# TB6560.net
KiCad netlist of a schematic drawn in Altium Designer
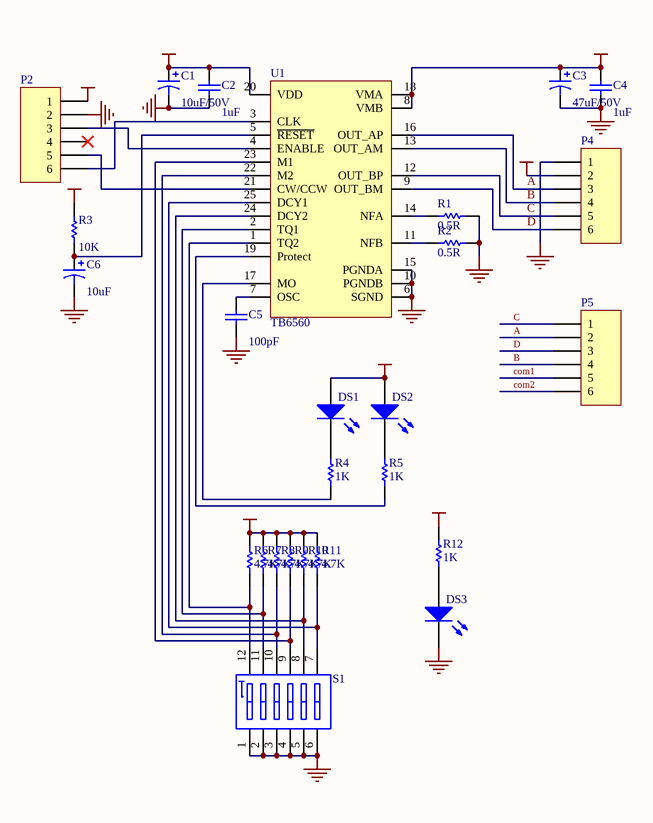
[diagram p0: 微步進驅動器TB6560.SCHDOC]

(export (version "E")
  (design (tool "Eeschema 10.0.6"))
  (components
    (comp (ref "C1")
      (value "10uF/50V")
      (footprint "CAPPR5-5x5")
      (description "Polarized Capacitor (Radial)")
      (fields (field (name "Comment") "Cap Pol1") (field (name "PUBLISHER") "Altium Limited"))
      (libsource (lib "Miscellaneous Devices") (part "Cap Pol1"))
    )
    (comp (ref "C2")
      (value "1uF")
      (footprint "CAPR5.08-7.8x3.2")
      (description "Capacitor")
      (fields (field (name "Comment") "Cap") (field (name "PUBLISHER") "Altium Limited"))
      (libsource (lib "Miscellaneous Devices") (part "Cap"))
    )
    (comp (ref "C3")
      (value "47uF/50V")
      (footprint "CAPPR5-5x5")
      (description "Polarized Capacitor (Radial)")
      (fields (field (name "Comment") "Cap Pol1") (field (name "PUBLISHER") "Altium Limited"))
      (libsource (lib "Miscellaneous Devices") (part "Cap Pol1"))
    )
    (comp (ref "C4")
      (value "1uF")
      (footprint "CAPR5.08-7.8x3.2")
      (description "Capacitor")
      (fields (field (name "Comment") "Cap") (field (name "PUBLISHER") "Altium Limited"))
      (libsource (lib "Miscellaneous Devices") (part "Cap"))
    )
    (comp (ref "C5")
      (value "100pF")
      (footprint "CAPR5.08-7.8x3.2")
      (description "Capacitor")
      (fields (field (name "Comment") "Cap") (field (name "PUBLISHER") "Altium Limited"))
      (libsource (lib "Miscellaneous Devices") (part "Cap"))
    )
    (comp (ref "C6")
      (value "10uF")
      (footprint "CAPPR5-5x5")
      (description "Polarized Capacitor (Radial)")
      (fields (field (name "Comment") "Cap Pol1") (field (name "PUBLISHER") "Altium Limited"))
      (libsource (lib "Miscellaneous Devices") (part "Cap Pol1"))
    )
    (comp (ref "DS1")
      (value "LED1")
      (footprint "LED 3mm T")
      (description "Typical RED GaAs LED")
      (fields (field (name "PUBLISHER") "Altium Limited"))
      (libsource (lib "Miscellaneous Devices") (part "LED1"))
    )
    (comp (ref "DS2")
      (value "LED1")
      (footprint "LED 3mm T")
      (description "Typical RED GaAs LED")
      (fields (field (name "PUBLISHER") "Altium Limited"))
      (libsource (lib "Miscellaneous Devices") (part "LED1"))
    )
    (comp (ref "DS3")
      (value "LED1")
      (footprint "LED 3mm T")
      (description "Typical RED GaAs LED")
      (fields (field (name "PUBLISHER") "Altium Limited"))
      (libsource (lib "Miscellaneous Devices") (part "LED1"))
    )
    (comp (ref "P2")
      (value "Header 6")
      (footprint "HDR1X6")
      (description "Header, 6-Pin")
      (fields (field (name "PUBLISHER") "Altium Limited"))
      (libsource (lib "") (part "Header 6_1"))
    )
    (comp (ref "P4")
      (value "Header 6")
      (footprint "6pinºÝ¤l-1")
      (description "Header, 6-Pin")
      (fields (field (name "PUBLISHER") "Altium Limited"))
      (libsource (lib "Miscellaneous Connectors") (part "Header 6"))
    )
    (comp (ref "P5")
      (value "Header 6")
      (footprint "HDR1X6")
      (description "Header, 6-Pin")
      (fields (field (name "PUBLISHER") "Altium Limited"))
      (libsource (lib "Miscellaneous Connectors") (part "Header 6"))
    )
    (comp (ref "R1")
      (value "0.5R")
      (footprint "¹qªý5.08mm")
      (description "Resistor")
      (fields (field (name "Comment") "Res1") (field (name "PUBLISHER") "Altium Limited"))
      (libsource (lib "Miscellaneous Devices") (part "Res1"))
    )
    (comp (ref "R2")
      (value "0.5R")
      (footprint "¹qªý5.08mm")
      (description "Resistor")
      (fields (field (name "Comment") "Res1") (field (name "PUBLISHER") "Altium Limited"))
      (libsource (lib "Miscellaneous Devices") (part "Res1"))
    )
    (comp (ref "R3")
      (value "10K")
      (footprint "AXIAL-0.3")
      (description "Resistor")
      (fields (field (name "Comment") "Res1") (field (name "PUBLISHER") "Altium Limited"))
      (libsource (lib "Miscellaneous Devices") (part "Res1"))
    )
    (comp (ref "R4")
      (value "1K")
      (footprint "AXIAL-0.3")
      (description "Resistor")
      (fields (field (name "Comment") "Res1") (field (name "PUBLISHER") "Altium Limited"))
      (libsource (lib "Miscellaneous Devices") (part "Res1"))
    )
    (comp (ref "R5")
      (value "1K")
      (footprint "AXIAL-0.3")
      (description "Resistor")
      (fields (field (name "Comment") "Res1") (field (name "PUBLISHER") "Altium Limited"))
      (libsource (lib "Miscellaneous Devices") (part "Res1"))
    )
    (comp (ref "R6")
      (value "4.7K")
      (footprint "AXIAL-0.3")
      (description "Resistor")
      (fields (field (name "Comment") "Res1") (field (name "PUBLISHER") "Altium Limited"))
      (libsource (lib "Miscellaneous Devices") (part "Res1"))
    )
    (comp (ref "R7")
      (value "4.7K")
      (footprint "AXIAL-0.3")
      (description "Resistor")
      (fields (field (name "Comment") "Res1") (field (name "PUBLISHER") "Altium Limited"))
      (libsource (lib "Miscellaneous Devices") (part "Res1"))
    )
    (comp (ref "R8")
      (value "4.7K")
      (footprint "AXIAL-0.3")
      (description "Resistor")
      (fields (field (name "Comment") "Res1") (field (name "PUBLISHER") "Altium Limited"))
      (libsource (lib "Miscellaneous Devices") (part "Res1"))
    )
    (comp (ref "R9")
      (value "4.7K")
      (footprint "AXIAL-0.3")
      (description "Resistor")
      (fields (field (name "Comment") "Res1") (field (name "PUBLISHER") "Altium Limited"))
      (libsource (lib "Miscellaneous Devices") (part "Res1"))
    )
    (comp (ref "R10")
      (value "4.7K")
      (footprint "AXIAL-0.3")
      (description "Resistor")
      (fields (field (name "Comment") "Res1") (field (name "PUBLISHER") "Altium Limited"))
      (libsource (lib "Miscellaneous Devices") (part "Res1"))
    )
    (comp (ref "R11")
      (value "4.7K")
      (footprint "AXIAL-0.3")
      (description "Resistor")
      (fields (field (name "Comment") "Res1") (field (name "PUBLISHER") "Altium Limited"))
      (libsource (lib "Miscellaneous Devices") (part "Res1"))
    )
    (comp (ref "R12")
      (value "1K")
      (footprint "AXIAL-0.3")
      (description "Resistor")
      (fields (field (name "Comment") "Res1") (field (name "PUBLISHER") "Altium Limited"))
      (libsource (lib "Miscellaneous Devices") (part "Res1"))
    )
    (comp (ref "S1")
      (value "SW DIP-6")
      (footprint "DIP-12/SW")
      (description "DIP Switch")
      (fields (field (name "PUBLISHER") "Altium Limited"))
      (libsource (lib "Miscellaneous Devices") (part "SW DIP-6"))
    )
    (comp (ref "U1") (value "TB6560") (footprint "TB6560AHQ") (libsource (lib "mydata") (part "TB6560")))
  )
  (nets
    (net (code "1") (name "+12") (class "Default")
      (node (ref "C3") (pin "1") (pinfunction "1_1") (pintype "passive"))
      (node (ref "C4") (pin "2") (pinfunction "2_2") (pintype "passive"))
      (node (ref "P4") (pin "2") (pinfunction "2_2") (pintype "passive"))
      (node (ref "U1") (pin "18") (pinfunction "VMA_18") (pintype "passive"))
      (node (ref "U1") (pin "8") (pinfunction "VMB_8") (pintype "passive"))
    )
    (net (code "2") (name "/A") (class "Default")
      (node (ref "P4") (pin "3") (pinfunction "3_3") (pintype "passive"))
      (node (ref "P5") (pin "2") (pinfunction "2_2") (pintype "passive"))
      (node (ref "U1") (pin "16") (pinfunction "OUT_AP_16") (pintype "passive"))
    )
    (net (code "3") (name "/B") (class "Default")
      (node (ref "P4") (pin "4") (pinfunction "4_4") (pintype "passive"))
      (node (ref "P5") (pin "4") (pinfunction "4_4") (pintype "passive"))
      (node (ref "U1") (pin "13") (pinfunction "OUT_AM_13") (pintype "passive"))
    )
    (net (code "4") (name "/C") (class "Default")
      (node (ref "P4") (pin "5") (pinfunction "5_5") (pintype "passive"))
      (node (ref "P5") (pin "1") (pinfunction "1_1") (pintype "passive"))
      (node (ref "U1") (pin "12") (pinfunction "OUT_BP_12") (pintype "passive"))
    )
    (net (code "5") (name "/D") (class "Default")
      (node (ref "P4") (pin "6") (pinfunction "6_6") (pintype "passive"))
      (node (ref "P5") (pin "3") (pinfunction "3_3") (pintype "passive"))
      (node (ref "U1") (pin "9") (pinfunction "OUT_BM_9") (pintype "passive"))
    )
    (net (code "6") (name "/com1") (class "Default")
      (node (ref "P5") (pin "5") (pinfunction "5_5") (pintype "passive"))
    )
    (net (code "7") (name "/com2") (class "Default")
      (node (ref "P5") (pin "6") (pinfunction "6_6") (pintype "passive"))
    )
    (net (code "8") (name "GND") (class "Default")
      (node (ref "C1") (pin "2") (pinfunction "2_2") (pintype "passive"))
      (node (ref "C2") (pin "1") (pinfunction "1_1") (pintype "passive"))
      (node (ref "C3") (pin "2") (pinfunction "2_2") (pintype "passive"))
      (node (ref "C4") (pin "1") (pinfunction "1_1") (pintype "passive"))
      (node (ref "C5") (pin "1") (pinfunction "1_1") (pintype "passive"))
      (node (ref "C6") (pin "2") (pinfunction "2_2") (pintype "passive"))
      (node (ref "DS3") (pin "2") (pinfunction "K_2") (pintype "passive"))
      (node (ref "P2") (pin "2") (pinfunction "2_2") (pintype "passive"))
      (node (ref "P4") (pin "1") (pinfunction "1_1") (pintype "passive"))
      (node (ref "R1") (pin "2") (pinfunction "2_2") (pintype "passive"))
      (node (ref "R2") (pin "2") (pinfunction "2_2") (pintype "passive"))
      (node (ref "S1") (pin "1") (pinfunction "A1_1") (pintype "passive"))
      (node (ref "S1") (pin "2") (pinfunction "A2_2") (pintype "passive"))
      (node (ref "S1") (pin "3") (pinfunction "A3_3") (pintype "passive"))
      (node (ref "S1") (pin "4") (pinfunction "A4_4") (pintype "passive"))
      (node (ref "S1") (pin "5") (pinfunction "A5_5") (pintype "passive"))
      (node (ref "S1") (pin "6") (pinfunction "A6_6") (pintype "passive"))
      (node (ref "U1") (pin "10") (pinfunction "PGNDB_10") (pintype "passive"))
      (node (ref "U1") (pin "15") (pinfunction "PGNDA_15") (pintype "passive"))
      (node (ref "U1") (pin "6") (pinfunction "SGND_6") (pintype "passive"))
    )
    (net (code "9") (name "Net-(DS1-K)") (class "Default")
      (node (ref "DS1") (pin "2") (pinfunction "K_2") (pintype "passive"))
      (node (ref "R4") (pin "2") (pinfunction "2_2") (pintype "passive"))
    )
    (net (code "10") (name "Net-(DS2-K)") (class "Default")
      (node (ref "DS2") (pin "2") (pinfunction "K_2") (pintype "passive"))
      (node (ref "R5") (pin "2") (pinfunction "2_2") (pintype "passive"))
    )
    (net (code "11") (name "Net-(DS3-A)") (class "Default")
      (node (ref "DS3") (pin "1") (pinfunction "A_1") (pintype "passive"))
      (node (ref "R12") (pin "1") (pinfunction "1_1") (pintype "passive"))
    )
    (net (code "12") (name "Net-(S1-B1)") (class "Default")
      (node (ref "R6") (pin "1") (pinfunction "1_1") (pintype "passive"))
      (node (ref "S1") (pin "12") (pinfunction "B1_12") (pintype "passive"))
      (node (ref "U1") (pin "1") (pinfunction "TQ2_1") (pintype "passive"))
    )
    (net (code "13") (name "Net-(S1-B2)") (class "Default")
      (node (ref "R7") (pin "1") (pinfunction "1_1") (pintype "passive"))
      (node (ref "S1") (pin "11") (pinfunction "B2_11") (pintype "passive"))
      (node (ref "U1") (pin "2") (pinfunction "TQ1_2") (pintype "passive"))
    )
    (net (code "14") (name "Net-(S1-B3)") (class "Default")
      (node (ref "R8") (pin "1") (pinfunction "1_1") (pintype "passive"))
      (node (ref "S1") (pin "10") (pinfunction "B3_10") (pintype "passive"))
      (node (ref "U1") (pin "22") (pinfunction "M2_22") (pintype "passive"))
    )
    (net (code "15") (name "Net-(S1-B4)") (class "Default")
      (node (ref "R9") (pin "1") (pinfunction "1_1") (pintype "passive"))
      (node (ref "S1") (pin "9") (pinfunction "B4_9") (pintype "passive"))
      (node (ref "U1") (pin "23") (pinfunction "M1_23") (pintype "passive"))
    )
    (net (code "16") (name "Net-(S1-B5)") (class "Default")
      (node (ref "R10") (pin "1") (pinfunction "1_1") (pintype "passive"))
      (node (ref "S1") (pin "8") (pinfunction "B5_8") (pintype "passive"))
      (node (ref "U1") (pin "24") (pinfunction "DCY2_24") (pintype "passive"))
    )
    (net (code "17") (name "Net-(S1-B6)") (class "Default")
      (node (ref "R11") (pin "1") (pinfunction "1_1") (pintype "passive"))
      (node (ref "S1") (pin "7") (pinfunction "B6_7") (pintype "passive"))
      (node (ref "U1") (pin "25") (pinfunction "DCY1_25") (pintype "passive"))
    )
    (net (code "18") (name "Net-(U1-CLK)") (class "Default")
      (node (ref "P2") (pin "6") (pinfunction "6_6") (pintype "passive"))
      (node (ref "U1") (pin "3") (pinfunction "CLK_3") (pintype "passive"))
    )
    (net (code "19") (name "Net-(U1-CW{slash}CCW)") (class "Default")
      (node (ref "P2") (pin "5") (pinfunction "5_5") (pintype "passive"))
      (node (ref "U1") (pin "21") (pinfunction "CW/CCW_21") (pintype "passive"))
    )
    (net (code "20") (name "Net-(U1-ENABLE)") (class "Default")
      (node (ref "P2") (pin "3") (pinfunction "3_3") (pintype "passive"))
      (node (ref "U1") (pin "4") (pinfunction "ENABLE_4") (pintype "passive"))
    )
    (net (code "21") (name "Net-(U1-MO)") (class "Default")
      (node (ref "R4") (pin "1") (pinfunction "1_1") (pintype "passive"))
      (node (ref "U1") (pin "17") (pinfunction "MO_17") (pintype "passive"))
    )
    (net (code "22") (name "Net-(U1-NFA)") (class "Default")
      (node (ref "R1") (pin "1") (pinfunction "1_1") (pintype "passive"))
      (node (ref "U1") (pin "14") (pinfunction "NFA_14") (pintype "passive"))
    )
    (net (code "23") (name "Net-(U1-NFB)") (class "Default")
      (node (ref "R2") (pin "1") (pinfunction "1_1") (pintype "passive"))
      (node (ref "U1") (pin "11") (pinfunction "NFB_11") (pintype "passive"))
    )
    (net (code "24") (name "Net-(U1-OSC)") (class "Default")
      (node (ref "C5") (pin "2") (pinfunction "2_2") (pintype "passive"))
      (node (ref "U1") (pin "7") (pinfunction "OSC_7") (pintype "passive"))
    )
    (net (code "25") (name "Net-(U1-Protect)") (class "Default")
      (node (ref "R5") (pin "1") (pinfunction "1_1") (pintype "passive"))
      (node (ref "U1") (pin "19") (pinfunction "Protect_19") (pintype "passive"))
    )
    (net (code "26") (name "Net-(U1-~{RESET})") (class "Default")
      (node (ref "C6") (pin "1") (pinfunction "1_1") (pintype "passive"))
      (node (ref "R3") (pin "1") (pinfunction "1_1") (pintype "passive"))
      (node (ref "U1") (pin "5") (pinfunction "~{RESET}_5") (pintype "passive"))
    )
    (net (code "27") (name "VCC") (class "Default")
      (node (ref "C1") (pin "1") (pinfunction "1_1") (pintype "passive"))
      (node (ref "C2") (pin "2") (pinfunction "2_2") (pintype "passive"))
      (node (ref "DS1") (pin "1") (pinfunction "A_1") (pintype "passive"))
      (node (ref "DS2") (pin "1") (pinfunction "A_1") (pintype "passive"))
      (node (ref "P2") (pin "1") (pinfunction "1_1") (pintype "passive"))
      (node (ref "R10") (pin "2") (pinfunction "2_2") (pintype "passive"))
      (node (ref "R11") (pin "2") (pinfunction "2_2") (pintype "passive"))
      (node (ref "R12") (pin "2") (pinfunction "2_2") (pintype "passive"))
      (node (ref "R3") (pin "2") (pinfunction "2_2") (pintype "passive"))
      (node (ref "R6") (pin "2") (pinfunction "2_2") (pintype "passive"))
      (node (ref "R7") (pin "2") (pinfunction "2_2") (pintype "passive"))
      (node (ref "R8") (pin "2") (pinfunction "2_2") (pintype "passive"))
      (node (ref "R9") (pin "2") (pinfunction "2_2") (pintype "passive"))
      (node (ref "U1") (pin "20") (pinfunction "VDD_20") (pintype "passive"))
    )
    (net (code "28") (name "unconnected-(P2-Pad4)") (class "Default")
      (node (ref "P2") (pin "4") (pinfunction "4_4") (pintype "passive+no_connect"))
    )
  )
)
